# FY_-_SUPPLY_BOARD.net
KiCad netlist of a schematic drawn in EAGLE
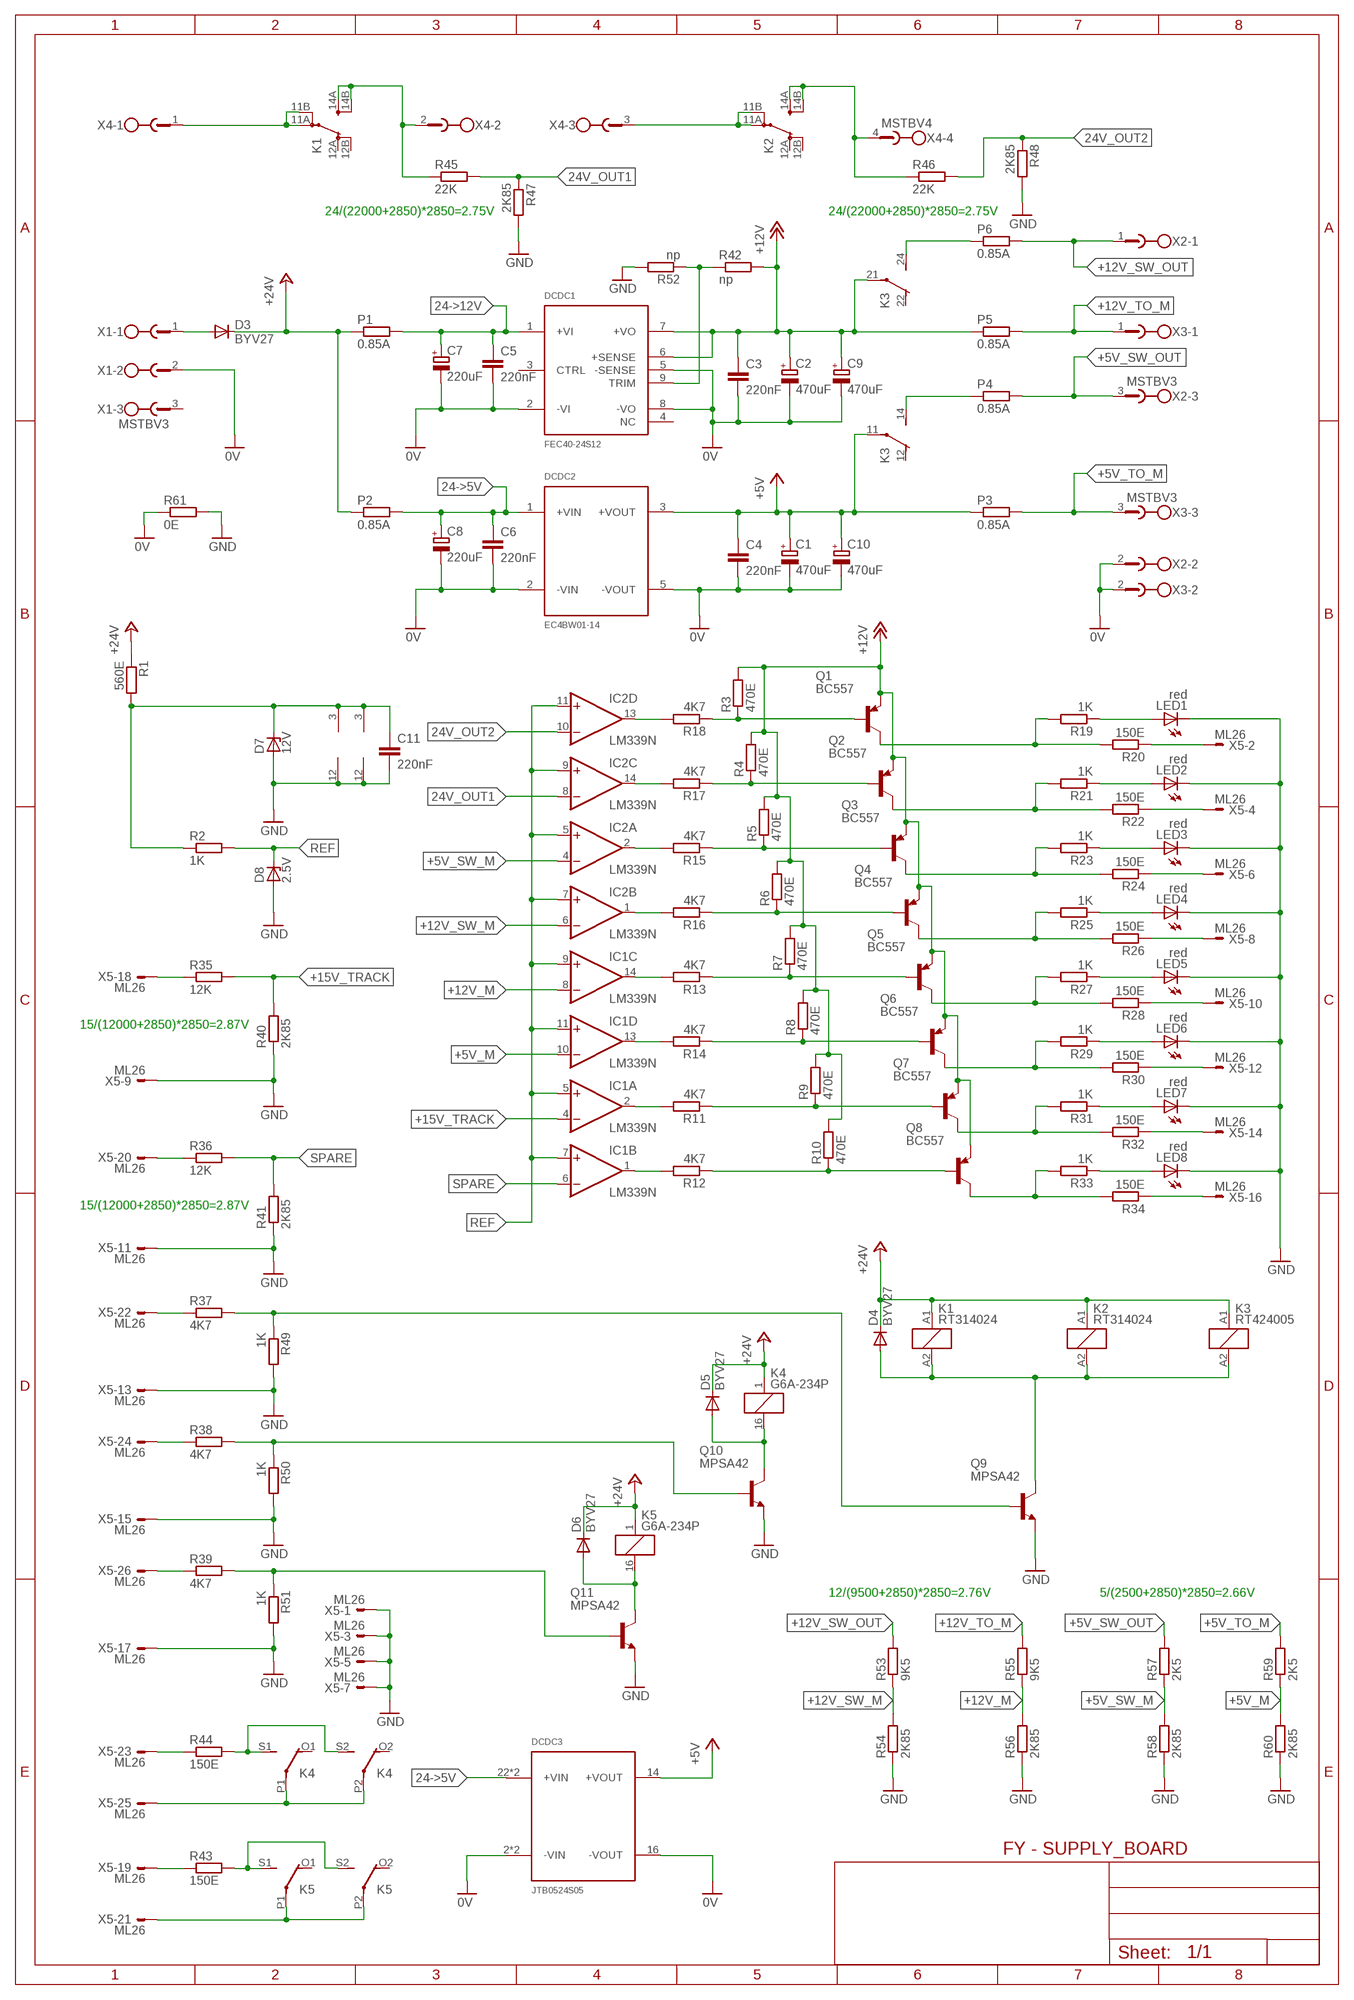
[diagram p0: schematic, sheet 1]

(export (version "E")
  (design (tool "Eeschema 10.0.6"))
  (components
    (comp (ref "C1")
      (value "470uF")
      (footprint "eagle-import:E5-10,5")
      (libsource (lib "eagle-import") (part "CPOL-EUE5-10.5"))
    )
    (comp (ref "C2")
      (value "470uF")
      (footprint "eagle-import:E5-10,5")
      (libsource (lib "eagle-import") (part "CPOL-EUE5-10.5"))
    )
    (comp (ref "C3")
      (value "220nF")
      (footprint "eagle-import:C050-025X075")
      (libsource (lib "eagle-import") (part "C-EU050-025X075"))
    )
    (comp (ref "C4")
      (value "220nF")
      (footprint "eagle-import:C050-025X075")
      (libsource (lib "eagle-import") (part "C-EU050-025X075"))
    )
    (comp (ref "C5")
      (value "220nF")
      (footprint "eagle-import:C050-025X075")
      (libsource (lib "eagle-import") (part "C-EU050-025X075"))
    )
    (comp (ref "C6")
      (value "220nF")
      (footprint "eagle-import:C050-025X075")
      (libsource (lib "eagle-import") (part "C-EU050-025X075"))
    )
    (comp (ref "C7")
      (value "220uF")
      (footprint "eagle-import:E5-10,5")
      (libsource (lib "eagle-import") (part "CPOL-EUE5-10.5"))
    )
    (comp (ref "C8")
      (value "220uF")
      (footprint "eagle-import:E5-10,5")
      (libsource (lib "eagle-import") (part "CPOL-EUE5-10.5"))
    )
    (comp (ref "C9")
      (value "470uF")
      (footprint "eagle-import:E5-10,5")
      (libsource (lib "eagle-import") (part "CPOL-EUE5-10.5"))
    )
    (comp (ref "C10")
      (value "470uF")
      (footprint "eagle-import:E5-10,5")
      (libsource (lib "eagle-import") (part "CPOL-EUE5-10.5"))
    )
    (comp (ref "C11")
      (value "220nF")
      (footprint "eagle-import:C050-025X075")
      (libsource (lib "eagle-import") (part "C-EU050-025X075"))
    )
    (comp (ref "D3")
      (value "BYV27")
      (footprint "eagle-import:SOD57-10")
      (libsource (lib "eagle-import") (part "BYV27"))
    )
    (comp (ref "D4")
      (value "BYV27")
      (footprint "eagle-import:SOD57-10")
      (libsource (lib "eagle-import") (part "BYV27"))
    )
    (comp (ref "D5")
      (value "BYV27")
      (footprint "eagle-import:SOD57-10")
      (libsource (lib "eagle-import") (part "BYV27"))
    )
    (comp (ref "D6")
      (value "BYV27")
      (footprint "eagle-import:SOD57-10")
      (libsource (lib "eagle-import") (part "BYV27"))
    )
    (comp (ref "D7")
      (value "12V")
      (footprint "eagle-import:ZDIO-7.5")
      (libsource (lib "eagle-import") (part "ZENER-DIODEZD-7.5"))
    )
    (comp (ref "D8")
      (value "2.5V")
      (footprint "eagle-import:ZDIO-7.5")
      (libsource (lib "eagle-import") (part "ZENER-DIODEZD-7.5"))
    )
    (comp (ref "DCDC1")
      (value "FEC40-24S12")
      (footprint "eagle-import:FEC40-24S12")
      (libsource (lib "eagle-import") (part "FEC40-24S12"))
    )
    (comp (ref "DCDC2")
      (value "EC4BW01-14")
      (footprint "eagle-import:EC4BW01-14")
      (libsource (lib "eagle-import") (part "EC4BW01-14"))
    )
    (comp (ref "DCDC3")
      (value "JTB0524S05")
      (footprint "eagle-import:XP_POWER_5W")
      (libsource (lib "eagle-import") (part "JTB0524S05_JTB0524S05"))
    )
    (comp (ref "IC1")
      (value "LM339N")
      (footprint "eagle-import:DIL14")
      (libsource (lib "eagle-import") (part "LM339N"))
    )
    (comp (ref "IC2")
      (value "LM339N")
      (footprint "eagle-import:DIL14")
      (libsource (lib "eagle-import") (part "LM339N"))
    )
    (comp (ref "K1")
      (value "RT314024")
      (footprint "eagle-import:RT-C_O16A5")
      (fields (field (name "MF") "TYCO ELECTRONICS"))
      (libsource (lib "eagle-import") (part "RT314024"))
    )
    (comp (ref "K2")
      (value "RT314024")
      (footprint "eagle-import:RT-C_O16A5")
      (fields (field (name "MF") "TYCO ELECTRONICS"))
      (libsource (lib "eagle-import") (part "RT314024"))
    )
    (comp (ref "K3")
      (value "RT424005")
      (footprint "eagle-import:RT2C_O")
      (libsource (lib "eagle-import") (part "RT42?4005"))
    )
    (comp (ref "K4")
      (value "G6A-234P")
      (footprint "eagle-import:G6A-234P")
      (libsource (lib "eagle-import") (part "G6A-234P"))
    )
    (comp (ref "K5")
      (value "G6A-234P")
      (footprint "eagle-import:G6A-234P")
      (libsource (lib "eagle-import") (part "G6A-234P"))
    )
    (comp (ref "LED1")
      (value "red")
      (footprint "eagle-import:LED3MM")
      (libsource (lib "eagle-import") (part "LED3MM"))
    )
    (comp (ref "LED2")
      (value "red")
      (footprint "eagle-import:LED3MM")
      (libsource (lib "eagle-import") (part "LED3MM"))
    )
    (comp (ref "LED3")
      (value "red")
      (footprint "eagle-import:LED3MM")
      (libsource (lib "eagle-import") (part "LED3MM"))
    )
    (comp (ref "LED4")
      (value "red")
      (footprint "eagle-import:LED3MM")
      (libsource (lib "eagle-import") (part "LED3MM"))
    )
    (comp (ref "LED5")
      (value "red")
      (footprint "eagle-import:LED3MM")
      (libsource (lib "eagle-import") (part "LED3MM"))
    )
    (comp (ref "LED6")
      (value "red")
      (footprint "eagle-import:LED3MM")
      (libsource (lib "eagle-import") (part "LED3MM"))
    )
    (comp (ref "LED7")
      (value "red")
      (footprint "eagle-import:LED3MM")
      (libsource (lib "eagle-import") (part "LED3MM"))
    )
    (comp (ref "LED8")
      (value "red")
      (footprint "eagle-import:LED3MM")
      (libsource (lib "eagle-import") (part "LED3MM"))
    )
    (comp (ref "P1")
      (value "0.85A")
      (footprint "eagle-import:0207_7")
      (libsource (lib "eagle-import") (part "R-EU_0207/7"))
    )
    (comp (ref "P2")
      (value "0.85A")
      (footprint "eagle-import:0207_7")
      (libsource (lib "eagle-import") (part "R-EU_0207/7"))
    )
    (comp (ref "P3")
      (value "0.85A")
      (footprint "eagle-import:0207_7")
      (libsource (lib "eagle-import") (part "R-EU_0207/7"))
    )
    (comp (ref "P4")
      (value "0.85A")
      (footprint "eagle-import:0207_7")
      (libsource (lib "eagle-import") (part "R-EU_0207/7"))
    )
    (comp (ref "P5")
      (value "0.85A")
      (footprint "eagle-import:0207_7")
      (libsource (lib "eagle-import") (part "R-EU_0207/7"))
    )
    (comp (ref "P6")
      (value "0.85A")
      (footprint "eagle-import:0207_7")
      (libsource (lib "eagle-import") (part "R-EU_0207/7"))
    )
    (comp (ref "Q1")
      (value "BC557")
      (footprint "eagle-import:TO92-EBC")
      (libsource (lib "eagle-import") (part "BC557"))
    )
    (comp (ref "Q2")
      (value "BC557")
      (footprint "eagle-import:TO92-EBC")
      (libsource (lib "eagle-import") (part "BC557"))
    )
    (comp (ref "Q3")
      (value "BC557")
      (footprint "eagle-import:TO92-EBC")
      (libsource (lib "eagle-import") (part "BC557"))
    )
    (comp (ref "Q4")
      (value "BC557")
      (footprint "eagle-import:TO92-EBC")
      (libsource (lib "eagle-import") (part "BC557"))
    )
    (comp (ref "Q5")
      (value "BC557")
      (footprint "eagle-import:TO92-EBC")
      (libsource (lib "eagle-import") (part "BC557"))
    )
    (comp (ref "Q6")
      (value "BC557")
      (footprint "eagle-import:TO92-EBC")
      (libsource (lib "eagle-import") (part "BC557"))
    )
    (comp (ref "Q7")
      (value "BC557")
      (footprint "eagle-import:TO92-EBC")
      (libsource (lib "eagle-import") (part "BC557"))
    )
    (comp (ref "Q8")
      (value "BC557")
      (footprint "eagle-import:TO92-EBC")
      (libsource (lib "eagle-import") (part "BC557"))
    )
    (comp (ref "Q9")
      (value "MPSA42")
      (footprint "eagle-import:TO92-CBE")
      (libsource (lib "eagle-import") (part "MPSA42TO92-CBE"))
    )
    (comp (ref "Q10")
      (value "MPSA42")
      (footprint "eagle-import:TO92-CBE")
      (libsource (lib "eagle-import") (part "MPSA42TO92-CBE"))
    )
    (comp (ref "Q11")
      (value "MPSA42")
      (footprint "eagle-import:TO92-CBE")
      (libsource (lib "eagle-import") (part "MPSA42TO92-CBE"))
    )
    (comp (ref "R1")
      (value "560E")
      (footprint "eagle-import:0411_15")
      (libsource (lib "eagle-import") (part "R-EU_0411/15"))
    )
    (comp (ref "R2")
      (value "1K")
      (footprint "eagle-import:0207_10")
      (libsource (lib "eagle-import") (part "R-EU_0207/10"))
    )
    (comp (ref "R3")
      (value "470E")
      (footprint "eagle-import:0207_10")
      (libsource (lib "eagle-import") (part "R-EU_0207/10"))
    )
    (comp (ref "R4")
      (value "470E")
      (footprint "eagle-import:0207_10")
      (libsource (lib "eagle-import") (part "R-EU_0207/10"))
    )
    (comp (ref "R5")
      (value "470E")
      (footprint "eagle-import:0207_10")
      (libsource (lib "eagle-import") (part "R-EU_0207/10"))
    )
    (comp (ref "R6")
      (value "470E")
      (footprint "eagle-import:0207_10")
      (libsource (lib "eagle-import") (part "R-EU_0207/10"))
    )
    (comp (ref "R7")
      (value "470E")
      (footprint "eagle-import:0207_10")
      (libsource (lib "eagle-import") (part "R-EU_0207/10"))
    )
    (comp (ref "R8")
      (value "470E")
      (footprint "eagle-import:0207_10")
      (libsource (lib "eagle-import") (part "R-EU_0207/10"))
    )
    (comp (ref "R9")
      (value "470E")
      (footprint "eagle-import:0207_10")
      (libsource (lib "eagle-import") (part "R-EU_0207/10"))
    )
    (comp (ref "R10")
      (value "470E")
      (footprint "eagle-import:0207_10")
      (libsource (lib "eagle-import") (part "R-EU_0207/10"))
    )
    (comp (ref "R11")
      (value "4K7")
      (footprint "eagle-import:0207_10")
      (libsource (lib "eagle-import") (part "R-EU_0207/10"))
    )
    (comp (ref "R12")
      (value "4K7")
      (footprint "eagle-import:0207_10")
      (libsource (lib "eagle-import") (part "R-EU_0207/10"))
    )
    (comp (ref "R13")
      (value "4K7")
      (footprint "eagle-import:0207_10")
      (libsource (lib "eagle-import") (part "R-EU_0207/10"))
    )
    (comp (ref "R14")
      (value "4K7")
      (footprint "eagle-import:0207_10")
      (libsource (lib "eagle-import") (part "R-EU_0207/10"))
    )
    (comp (ref "R15")
      (value "4K7")
      (footprint "eagle-import:0207_10")
      (libsource (lib "eagle-import") (part "R-EU_0207/10"))
    )
    (comp (ref "R16")
      (value "4K7")
      (footprint "eagle-import:0207_10")
      (libsource (lib "eagle-import") (part "R-EU_0207/10"))
    )
    (comp (ref "R17")
      (value "4K7")
      (footprint "eagle-import:0207_10")
      (libsource (lib "eagle-import") (part "R-EU_0207/10"))
    )
    (comp (ref "R18")
      (value "4K7")
      (footprint "eagle-import:0207_10")
      (libsource (lib "eagle-import") (part "R-EU_0207/10"))
    )
    (comp (ref "R19")
      (value "1K")
      (footprint "eagle-import:0207_10")
      (libsource (lib "eagle-import") (part "R-EU_0207/10"))
    )
    (comp (ref "R20")
      (value "150E")
      (footprint "eagle-import:0207_10")
      (libsource (lib "eagle-import") (part "R-EU_0207/10"))
    )
    (comp (ref "R21")
      (value "1K")
      (footprint "eagle-import:0207_10")
      (libsource (lib "eagle-import") (part "R-EU_0207/10"))
    )
    (comp (ref "R22")
      (value "150E")
      (footprint "eagle-import:0207_10")
      (libsource (lib "eagle-import") (part "R-EU_0207/10"))
    )
    (comp (ref "R23")
      (value "1K")
      (footprint "eagle-import:0207_10")
      (libsource (lib "eagle-import") (part "R-EU_0207/10"))
    )
    (comp (ref "R24")
      (value "150E")
      (footprint "eagle-import:0207_10")
      (libsource (lib "eagle-import") (part "R-EU_0207/10"))
    )
    (comp (ref "R25")
      (value "1K")
      (footprint "eagle-import:0207_10")
      (libsource (lib "eagle-import") (part "R-EU_0207/10"))
    )
    (comp (ref "R26")
      (value "150E")
      (footprint "eagle-import:0207_10")
      (libsource (lib "eagle-import") (part "R-EU_0207/10"))
    )
    (comp (ref "R27")
      (value "1K")
      (footprint "eagle-import:0207_10")
      (libsource (lib "eagle-import") (part "R-EU_0207/10"))
    )
    (comp (ref "R28")
      (value "150E")
      (footprint "eagle-import:0207_10")
      (libsource (lib "eagle-import") (part "R-EU_0207/10"))
    )
    (comp (ref "R29")
      (value "1K")
      (footprint "eagle-import:0207_10")
      (libsource (lib "eagle-import") (part "R-EU_0207/10"))
    )
    (comp (ref "R30")
      (value "150E")
      (footprint "eagle-import:0207_10")
      (libsource (lib "eagle-import") (part "R-EU_0207/10"))
    )
    (comp (ref "R31")
      (value "1K")
      (footprint "eagle-import:0207_10")
      (libsource (lib "eagle-import") (part "R-EU_0207/10"))
    )
    (comp (ref "R32")
      (value "150E")
      (footprint "eagle-import:0207_10")
      (libsource (lib "eagle-import") (part "R-EU_0207/10"))
    )
    (comp (ref "R33")
      (value "1K")
      (footprint "eagle-import:0207_10")
      (libsource (lib "eagle-import") (part "R-EU_0207/10"))
    )
    (comp (ref "R34")
      (value "150E")
      (footprint "eagle-import:0207_10")
      (libsource (lib "eagle-import") (part "R-EU_0207/10"))
    )
    (comp (ref "R35")
      (value "12K")
      (footprint "eagle-import:0207_10")
      (libsource (lib "eagle-import") (part "R-EU_0207/10"))
    )
    (comp (ref "R36")
      (value "12K")
      (footprint "eagle-import:0207_10")
      (libsource (lib "eagle-import") (part "R-EU_0207/10"))
    )
    (comp (ref "R37")
      (value "4K7")
      (footprint "eagle-import:0207_10")
      (libsource (lib "eagle-import") (part "R-EU_0207/10"))
    )
    (comp (ref "R38")
      (value "4K7")
      (footprint "eagle-import:0207_10")
      (libsource (lib "eagle-import") (part "R-EU_0207/10"))
    )
    (comp (ref "R39")
      (value "4K7")
      (footprint "eagle-import:0207_10")
      (libsource (lib "eagle-import") (part "R-EU_0207/10"))
    )
    (comp (ref "R40")
      (value "2K85")
      (footprint "eagle-import:0207_10")
      (libsource (lib "eagle-import") (part "R-EU_0207/10"))
    )
    (comp (ref "R41")
      (value "2K85")
      (footprint "eagle-import:0207_10")
      (libsource (lib "eagle-import") (part "R-EU_0207/10"))
    )
    (comp (ref "R42")
      (value "np")
      (footprint "eagle-import:0207_10")
      (libsource (lib "eagle-import") (part "R-EU_0207/10"))
    )
    (comp (ref "R43")
      (value "150E")
      (footprint "eagle-import:0922_11")
      (libsource (lib "eagle-import") (part "R-EU_0922/11"))
    )
    (comp (ref "R44")
      (value "150E")
      (footprint "eagle-import:0922_11")
      (libsource (lib "eagle-import") (part "R-EU_0922/11"))
    )
    (comp (ref "R45")
      (value "22K")
      (footprint "eagle-import:0207_10")
      (libsource (lib "eagle-import") (part "R-EU_0207/10"))
    )
    (comp (ref "R46")
      (value "22K")
      (footprint "eagle-import:0207_10")
      (libsource (lib "eagle-import") (part "R-EU_0207/10"))
    )
    (comp (ref "R47")
      (value "2K85")
      (footprint "eagle-import:0207_10")
      (libsource (lib "eagle-import") (part "R-EU_0207/10"))
    )
    (comp (ref "R48")
      (value "2K85")
      (footprint "eagle-import:0207_10")
      (libsource (lib "eagle-import") (part "R-EU_0207/10"))
    )
    (comp (ref "R49")
      (value "1K")
      (footprint "eagle-import:0207_10")
      (libsource (lib "eagle-import") (part "R-EU_0207/10"))
    )
    (comp (ref "R50")
      (value "1K")
      (footprint "eagle-import:0207_10")
      (libsource (lib "eagle-import") (part "R-EU_0207/10"))
    )
    (comp (ref "R51")
      (value "1K")
      (footprint "eagle-import:0207_10")
      (libsource (lib "eagle-import") (part "R-EU_0207/10"))
    )
    (comp (ref "R52")
      (value "np")
      (footprint "eagle-import:0207_10")
      (libsource (lib "eagle-import") (part "R-EU_0207/10"))
    )
    (comp (ref "R53")
      (value "9K5")
      (footprint "eagle-import:0207_10")
      (libsource (lib "eagle-import") (part "R-EU_0207/10"))
    )
    (comp (ref "R54")
      (value "2K85")
      (footprint "eagle-import:0207_10")
      (libsource (lib "eagle-import") (part "R-EU_0207/10"))
    )
    (comp (ref "R55")
      (value "9K5")
      (footprint "eagle-import:0207_10")
      (libsource (lib "eagle-import") (part "R-EU_0207/10"))
    )
    (comp (ref "R56")
      (value "2K85")
      (footprint "eagle-import:0207_10")
      (libsource (lib "eagle-import") (part "R-EU_0207/10"))
    )
    (comp (ref "R57")
      (value "2K5")
      (footprint "eagle-import:0207_10")
      (libsource (lib "eagle-import") (part "R-EU_0207/10"))
    )
    (comp (ref "R58")
      (value "2K85")
      (footprint "eagle-import:0207_10")
      (libsource (lib "eagle-import") (part "R-EU_0207/10"))
    )
    (comp (ref "R59")
      (value "2K5")
      (footprint "eagle-import:0207_10")
      (libsource (lib "eagle-import") (part "R-EU_0207/10"))
    )
    (comp (ref "R60")
      (value "2K85")
      (footprint "eagle-import:0207_10")
      (libsource (lib "eagle-import") (part "R-EU_0207/10"))
    )
    (comp (ref "R61")
      (value "0E")
      (footprint "eagle-import:0204V")
      (libsource (lib "eagle-import") (part "resistor_R-EU_0204/2V"))
    )
    (comp (ref "X1")
      (value "MSTBV3")
      (footprint "eagle-import:MSTBV3")
      (fields (field (name "MPN") "MSTBV 2,5/3-GF-5.08"))
      (libsource (lib "eagle-import") (part "MSTBV3"))
    )
    (comp (ref "X2")
      (value "MSTBV3")
      (footprint "eagle-import:MSTBV3")
      (fields (field (name "MPN") "MSTBV 2,5/3-GF-5.08"))
      (libsource (lib "eagle-import") (part "MSTBV3"))
    )
    (comp (ref "X3")
      (value "MSTBV3")
      (footprint "eagle-import:MSTBV3")
      (fields (field (name "MPN") "MSTBV 2,5/3-GF-5.08"))
      (libsource (lib "eagle-import") (part "MSTBV3"))
    )
    (comp (ref "X4")
      (value "MSTBV4")
      (footprint "eagle-import:MSTBV4")
      (fields (field (name "MPN") "MSTBV 2,5/4-GF-5.08"))
      (libsource (lib "eagle-import") (part "MSTBV4"))
    )
    (comp (ref "X5")
      (value "ML26")
      (footprint "eagle-import:ML26")
      (libsource (lib "eagle-import") (part "ML26?E"))
    )
  )
  (nets
    (net (code "1") (name "+5V") (class "Default")
      (node (ref "C1") (pin "+") (pinfunction "+_+") (pintype "passive"))
      (node (ref "C10") (pin "+") (pinfunction "+_+") (pintype "passive"))
      (node (ref "C4") (pin "1") (pinfunction "1_1") (pintype "passive"))
      (node (ref "DCDC2") (pin "3") (pinfunction "+VOUT_3") (pintype "passive"))
      (node (ref "DCDC3") (pin "14") (pinfunction "+VOUT_14") (pintype "passive"))
      (node (ref "K3") (pin "11") (pinfunction "P_11") (pintype "passive"))
      (node (ref "P3") (pin "1") (pinfunction "1_1") (pintype "passive"))
    )
    (net (code "2") (name "+5V_M") (class "Default")
      (node (ref "IC1") (pin "10") (pinfunction "-IN_10") (pintype "input"))
      (node (ref "R59") (pin "1") (pinfunction "1_1") (pintype "passive"))
      (node (ref "R60") (pin "2") (pinfunction "2_2") (pintype "passive"))
    )
    (net (code "3") (name "+5V_SW_M") (class "Default")
      (node (ref "IC2") (pin "4") (pinfunction "-IN_4") (pintype "input"))
      (node (ref "R57") (pin "1") (pinfunction "1_1") (pintype "passive"))
      (node (ref "R58") (pin "2") (pinfunction "2_2") (pintype "passive"))
    )
    (net (code "4") (name "+5V_SW_OUT") (class "Default")
      (node (ref "P4") (pin "2") (pinfunction "2_2") (pintype "passive"))
      (node (ref "R57") (pin "2") (pinfunction "2_2") (pintype "passive"))
      (node (ref "X2") (pin "3") (pinfunction "1_3") (pintype "passive"))
    )
    (net (code "5") (name "+5V_TO_M") (class "Default")
      (node (ref "P3") (pin "2") (pinfunction "2_2") (pintype "passive"))
      (node (ref "R59") (pin "2") (pinfunction "2_2") (pintype "passive"))
      (node (ref "X3") (pin "3") (pinfunction "1_3") (pintype "passive"))
    )
    (net (code "6") (name "+12V") (class "Default")
      (node (ref "C2") (pin "+") (pinfunction "+_+") (pintype "passive"))
      (node (ref "C3") (pin "1") (pinfunction "1_1") (pintype "passive"))
      (node (ref "C9") (pin "+") (pinfunction "+_+") (pintype "passive"))
      (node (ref "DCDC1") (pin "6") (pinfunction "+SENSE_6") (pintype "passive"))
      (node (ref "DCDC1") (pin "7") (pinfunction "+VO_7") (pintype "passive"))
      (node (ref "K3") (pin "21") (pinfunction "P_21") (pintype "passive"))
      (node (ref "P5") (pin "1") (pinfunction "1_1") (pintype "passive"))
      (node (ref "Q1") (pin "E") (pinfunction "E_E") (pintype "passive"))
      (node (ref "Q2") (pin "E") (pinfunction "E_E") (pintype "passive"))
      (node (ref "Q3") (pin "E") (pinfunction "E_E") (pintype "passive"))
      (node (ref "Q4") (pin "E") (pinfunction "E_E") (pintype "passive"))
      (node (ref "Q5") (pin "E") (pinfunction "E_E") (pintype "passive"))
      (node (ref "Q6") (pin "E") (pinfunction "E_E") (pintype "passive"))
      (node (ref "Q7") (pin "E") (pinfunction "E_E") (pintype "passive"))
      (node (ref "Q8") (pin "E") (pinfunction "E_E") (pintype "passive"))
      (node (ref "R10") (pin "2") (pinfunction "2_2") (pintype "passive"))
      (node (ref "R3") (pin "2") (pinfunction "2_2") (pintype "passive"))
      (node (ref "R4") (pin "2") (pinfunction "2_2") (pintype "passive"))
      (node (ref "R42") (pin "2") (pinfunction "2_2") (pintype "passive"))
      (node (ref "R5") (pin "2") (pinfunction "2_2") (pintype "passive"))
      (node (ref "R6") (pin "2") (pinfunction "2_2") (pintype "passive"))
      (node (ref "R7") (pin "2") (pinfunction "2_2") (pintype "passive"))
      (node (ref "R8") (pin "2") (pinfunction "2_2") (pintype "passive"))
      (node (ref "R9") (pin "2") (pinfunction "2_2") (pintype "passive"))
    )
    (net (code "7") (name "+12V_M") (class "Default")
      (node (ref "IC1") (pin "8") (pinfunction "-IN_8") (pintype "input"))
      (node (ref "R55") (pin "1") (pinfunction "1_1") (pintype "passive"))
      (node (ref "R56") (pin "2") (pinfunction "2_2") (pintype "passive"))
    )
    (net (code "8") (name "+12V_SW_M") (class "Default")
      (node (ref "IC2") (pin "6") (pinfunction "-IN_6") (pintype "input"))
      (node (ref "R53") (pin "1") (pinfunction "1_1") (pintype "passive"))
      (node (ref "R54") (pin "2") (pinfunction "2_2") (pintype "passive"))
    )
    (net (code "9") (name "+12V_SW_OUT") (class "Default")
      (node (ref "P6") (pin "2") (pinfunction "2_2") (pintype "passive"))
      (node (ref "R53") (pin "2") (pinfunction "2_2") (pintype "passive"))
      (node (ref "X2") (pin "1") (pinfunction "1_1") (pintype "passive"))
    )
    (net (code "10") (name "+12V_TO_M") (class "Default")
      (node (ref "P5") (pin "2") (pinfunction "2_2") (pintype "passive"))
      (node (ref "R55") (pin "2") (pinfunction "2_2") (pintype "passive"))
      (node (ref "X3") (pin "1") (pinfunction "1_1") (pintype "passive"))
    )
    (net (code "11") (name "+15V_TRACK") (class "Default")
      (node (ref "IC1") (pin "4") (pinfunction "-IN_4") (pintype "input"))
      (node (ref "R35") (pin "2") (pinfunction "2_2") (pintype "passive"))
      (node (ref "R40") (pin "2") (pinfunction "2_2") (pintype "passive"))
    )
    (net (code "12") (name "+24V") (class "Default")
      (node (ref "D3") (pin "C") (pinfunction "C_C") (pintype "passive"))
      (node (ref "D4") (pin "C") (pinfunction "C_C") (pintype "passive"))
      (node (ref "D5") (pin "C") (pinfunction "C_C") (pintype "passive"))
      (node (ref "D6") (pin "C") (pinfunction "C_C") (pintype "passive"))
      (node (ref "K1") (pin "A1") (pinfunction "1_A1") (pintype "passive"))
      (node (ref "K2") (pin "A1") (pinfunction "1_A1") (pintype "passive"))
      (node (ref "K3") (pin "A1") (pinfunction "1_A1") (pintype "passive"))
      (node (ref "K4") (pin "1") (pinfunction "1_1") (pintype "passive"))
      (node (ref "K5") (pin "1") (pinfunction "1_1") (pintype "passive"))
      (node (ref "P1") (pin "1") (pinfunction "1_1") (pintype "passive"))
      (node (ref "P2") (pin "1") (pinfunction "1_1") (pintype "passive"))
      (node (ref "R1") (pin "1") (pinfunction "1_1") (pintype "passive"))
    )
    (net (code "13") (name "0V") (class "Default")
      (node (ref "C1") (pin "-") (pinfunction "-_-") (pintype "passive"))
      (node (ref "C10") (pin "-") (pinfunction "-_-") (pintype "passive"))
      (node (ref "C2") (pin "-") (pinfunction "-_-") (pintype "passive"))
      (node (ref "C3") (pin "2") (pinfunction "2_2") (pintype "passive"))
      (node (ref "C4") (pin "2") (pinfunction "2_2") (pintype "passive"))
      (node (ref "C5") (pin "2") (pinfunction "2_2") (pintype "passive"))
      (node (ref "C6") (pin "2") (pinfunction "2_2") (pintype "passive"))
      (node (ref "C7") (pin "-") (pinfunction "-_-") (pintype "passive"))
      (node (ref "C8") (pin "-") (pinfunction "-_-") (pintype "passive"))
      (node (ref "C9") (pin "-") (pinfunction "-_-") (pintype "passive"))
      (node (ref "DCDC1") (pin "2") (pinfunction "-VI_2") (pintype "passive"))
      (node (ref "DCDC1") (pin "5") (pinfunction "-SENSE_5") (pintype "passive"))
      (node (ref "DCDC1") (pin "8") (pinfunction "-VO_8") (pintype "passive"))
      (node (ref "DCDC2") (pin "2") (pinfunction "-VIN_2") (pintype "passive"))
      (node (ref "DCDC2") (pin "5") (pinfunction "-VOUT_5") (pintype "passive"))
      (node (ref "DCDC3") (pin "16") (pinfunction "-VOUT_16") (pintype "passive"))
      (node (ref "DCDC3") (pin "2") (pinfunction "-VIN_2") (pintype "passive"))
      (node (ref "DCDC3") (pin "3") (pinfunction "-VIN_3") (pintype "passive"))
      (node (ref "R61") (pin "1") (pinfunction "1_1") (pintype "passive"))
      (node (ref "X1") (pin "2") (pinfunction "1_2") (pintype "passive"))
      (node (ref "X2") (pin "2") (pinfunction "1_2") (pintype "passive"))
      (node (ref "X3") (pin "2") (pinfunction "1_2") (pintype "passive"))
    )
    (net (code "14") (name "24->5V") (class "Default")
      (node (ref "C6") (pin "1") (pinfunction "1_1") (pintype "passive"))
      (node (ref "C8") (pin "+") (pinfunction "+_+") (pintype "passive"))
      (node (ref "DCDC2") (pin "1") (pinfunction "+VIN_1") (pintype "passive"))
      (node (ref "DCDC3") (pin "22") (pinfunction "+VIN_22") (pintype "passive"))
      (node (ref "DCDC3") (pin "23") (pinfunction "+VIN_23") (pintype "passive"))
      (node (ref "P2") (pin "2") (pinfunction "2_2") (pintype "passive"))
    )
    (net (code "15") (name "24->12V") (class "Default")
      (node (ref "C5") (pin "1") (pinfunction "1_1") (pintype "passive"))
      (node (ref "C7") (pin "+") (pinfunction "+_+") (pintype "passive"))
      (node (ref "DCDC1") (pin "1") (pinfunction "+VI_1") (pintype "passive"))
      (node (ref "P1") (pin "2") (pinfunction "2_2") (pintype "passive"))
    )
    (net (code "16") (name "24V_OUT1") (class "Default")
      (node (ref "IC2") (pin "8") (pinfunction "-IN_8") (pintype "input"))
      (node (ref "R45") (pin "2") (pinfunction "2_2") (pintype "passive"))
      (node (ref "R47") (pin "1") (pinfunction "1_1") (pintype "passive"))
    )
    (net (code "17") (name "24V_OUT2") (class "Default")
      (node (ref "IC2") (pin "10") (pinfunction "-IN_10") (pintype "input"))
      (node (ref "R46") (pin "2") (pinfunction "2_2") (pintype "passive"))
      (node (ref "R48") (pin "1") (pinfunction "1_1") (pintype "passive"))
    )
    (net (code "18") (name "GND") (class "Default")
      (node (ref "C11") (pin "2") (pinfunction "2_2") (pintype "passive"))
      (node (ref "D7") (pin "A") (pinfunction "A_A") (pintype "passive"))
      (node (ref "D8") (pin "A") (pinfunction "A_A") (pintype "passive"))
      (node (ref "IC1") (pin "12") (pinfunction "GND_12") (pintype "power_in"))
      (node (ref "IC2") (pin "12") (pinfunction "GND_12") (pintype "power_in"))
      (node (ref "LED1") (pin "K") (pinfunction "C_K") (pintype "passive"))
      (node (ref "LED2") (pin "K") (pinfunction "C_K") (pintype "passive"))
      (node (ref "LED3") (pin "K") (pinfunction "C_K") (pintype "passive"))
      (node (ref "LED4") (pin "K") (pinfunction "C_K") (pintype "passive"))
      (node (ref "LED5") (pin "K") (pinfunction "C_K") (pintype "passive"))
      (node (ref "LED6") (pin "K") (pinfunction "C_K") (pintype "passive"))
      (node (ref "LED7") (pin "K") (pinfunction "C_K") (pintype "passive"))
      (node (ref "LED8") (pin "K") (pinfunction "C_K") (pintype "passive"))
      (node (ref "Q10") (pin "E") (pinfunction "E_E") (pintype "passive"))
      (node (ref "Q11") (pin "E") (pinfunction "E_E") (pintype "passive"))
      (node (ref "Q9") (pin "E") (pinfunction "E_E") (pintype "passive"))
      (node (ref "R40") (pin "1") (pinfunction "1_1") (pintype "passive"))
      (node (ref "R41") (pin "1") (pinfunction "1_1") (pintype "passive"))
      (node (ref "R47") (pin "2") (pinfunction "2_2") (pintype "passive"))
      (node (ref "R48") (pin "2") (pinfunction "2_2") (pintype "passive"))
      (node (ref "R49") (pin "2") (pinfunction "2_2") (pintype "passive"))
      (node (ref "R50") (pin "2") (pinfunction "2_2") (pintype "passive"))
      (node (ref "R51") (pin "2") (pinfunction "2_2") (pintype "passive"))
      (node (ref "R52") (pin "2") (pinfunction "2_2") (pintype "passive"))
      (node (ref "R54") (pin "1") (pinfunction "1_1") (pintype "passive"))
      (node (ref "R56") (pin "1") (pinfunction "1_1") (pintype "passive"))
      (node (ref "R58") (pin "1") (pinfunction "1_1") (pintype "passive"))
      (node (ref "R60") (pin "1") (pinfunction "1_1") (pintype "passive"))
      (node (ref "R61") (pin "2") (pinfunction "2_2") (pintype "passive"))
      (node (ref "X5") (pin "1") (pinfunction "S_1") (pintype "passive"))
      (node (ref "X5") (pin "11") (pinfunction "S_11") (pintype "passive"))
      (node (ref "X5") (pin "13") (pinfunction "S_13") (pintype "passive"))
      (node (ref "X5") (pin "15") (pinfunction "S_15") (pintype "passive"))
      (node (ref "X5") (pin "17") (pinfunction "S_17") (pintype "passive"))
      (node (ref "X5") (pin "3") (pinfunction "S_3") (pintype "passive"))
      (node (ref "X5") (pin "5") (pinfunction "S_5") (pintype "passive"))
      (node (ref "X5") (pin "7") (pinfunction "S_7") (pintype "passive"))
      (node (ref "X5") (pin "9") (pinfunction "S_9") (pintype "passive"))
    )
    (net (code "19") (name "Net-(D3-PadA)") (class "Default")
      (node (ref "D3") (pin "A") (pinfunction "A_A") (pintype "passive"))
      (node (ref "X1") (pin "1") (pinfunction "1_1") (pintype "passive"))
    )
    (net (code "20") (name "Net-(DCDC1-TRIM)") (class "Default")
      (node (ref "DCDC1") (pin "9") (pinfunction "TRIM_9") (pintype "passive"))
      (node (ref "R42") (pin "1") (pinfunction "1_1") (pintype "passive"))
      (node (ref "R52") (pin "1") (pinfunction "1_1") (pintype "passive"))
    )
    (net (code "21") (name "Net-(IC1A-OUT)") (class "Default")
      (node (ref "IC1") (pin "2") (pinfunction "OUT_2") (pintype "open_collector"))
      (node (ref "R11") (pin "2") (pinfunction "2_2") (pintype "passive"))
    )
    (net (code "22") (name "Net-(IC1B-OUT)") (class "Default")
      (node (ref "IC1") (pin "1") (pinfunction "OUT_1") (pintype "open_collector"))
      (node (ref "R12") (pin "2") (pinfunction "2_2") (pintype "passive"))
    )
    (net (code "23") (name "Net-(IC1C-OUT)") (class "Default")
      (node (ref "IC1") (pin "14") (pinfunction "OUT_14") (pintype "open_collector"))
      (node (ref "R13") (pin "2") (pinfunction "2_2") (pintype "passive"))
    )
    (net (code "24") (name "Net-(IC1D-OUT)") (class "Default")
      (node (ref "IC1") (pin "13") (pinfunction "OUT_13") (pintype "open_collector"))
      (node (ref "R14") (pin "2") (pinfunction "2_2") (pintype "passive"))
    )
    (net (code "25") (name "Net-(IC1E-V+)") (class "Default")
      (node (ref "C11") (pin "1") (pinfunction "1_1") (pintype "passive"))
      (node (ref "D7") (pin "C") (pinfunction "C_C") (pintype "passive"))
      (node (ref "IC1") (pin "3") (pinfunction "V+_3") (pintype "power_in"))
      (node (ref "IC2") (pin "3") (pinfunction "V+_3") (pintype "power_in"))
      (node (ref "R1") (pin "2") (pinfunction "2_2") (pintype "passive"))
      (node (ref "R2") (pin "1") (pinfunction "1_1") (pintype "passive"))
    )
    (net (code "26") (name "Net-(IC2A-OUT)") (class "Default")
      (node (ref "IC2") (pin "2") (pinfunction "OUT_2") (pintype "open_collector"))
      (node (ref "R15") (pin "2") (pinfunction "2_2") (pintype "passive"))
    )
    (net (code "27") (name "Net-(IC2B-OUT)") (class "Default")
      (node (ref "IC2") (pin "1") (pinfunction "OUT_1") (pintype "open_collector"))
      (node (ref "R16") (pin "2") (pinfunction "2_2") (pintype "passive"))
    )
    (net (code "28") (name "Net-(IC2C-OUT)") (class "Default")
      (node (ref "IC2") (pin "14") (pinfunction "OUT_14") (pintype "open_collector"))
      (node (ref "R17") (pin "2") (pinfunction "2_2") (pintype "passive"))
    )
    (net (code "29") (name "Net-(IC2D-OUT)") (class "Default")
      (node (ref "IC2") (pin "13") (pinfunction "OUT_13") (pintype "open_collector"))
      (node (ref "R18") (pin "2") (pinfunction "2_2") (pintype "passive"))
    )
    (net (code "30") (name "Net-(K1A-2)") (class "Default")
      (node (ref "D4") (pin "A") (pinfunction "A_A") (pintype "passive"))
      (node (ref "K1") (pin "A2") (pinfunction "2_A2") (pintype "passive"))
      (node (ref "K2") (pin "A2") (pinfunction "2_A2") (pintype "passive"))
      (node (ref "K3") (pin "A2") (pinfunction "2_A2") (pintype "passive"))
      (node (ref "Q9") (pin "C") (pinfunction "C_C") (pintype "passive"))
    )
    (net (code "31") (name "Net-(K1B-PA)") (class "Default")
      (node (ref "K1") (pin "11A") (pinfunction "PA_11A") (pintype "passive"))
      (node (ref "K1") (pin "11B") (pinfunction "PB_11B") (pintype "passive"))
      (node (ref "X4") (pin "1") (pinfunction "1_1") (pintype "passive"))
    )
    (net (code "32") (name "Net-(K1B-SA)") (class "Default")
      (node (ref "K1") (pin "14A") (pinfunction "SA_14A") (pintype "passive"))
      (node (ref "K1") (pin "14B") (pinfunction "SB_14B") (pintype "passive"))
      (node (ref "R45") (pin "1") (pinfunction "1_1") (pintype "passive"))
      (node (ref "X4") (pin "2") (pinfunction "1_2") (pintype "passive"))
    )
    (net (code "33") (name "Net-(K2B-PA)") (class "Default")
      (node (ref "K2") (pin "11A") (pinfunction "PA_11A") (pintype "passive"))
      (node (ref "K2") (pin "11B") (pinfunction "PB_11B") (pintype "passive"))
      (node (ref "X4") (pin "3") (pinfunction "1_3") (pintype "passive"))
    )
    (net (code "34") (name "Net-(K2B-SA)") (class "Default")
      (node (ref "K2") (pin "14A") (pinfunction "SA_14A") (pintype "passive"))
      (node (ref "K2") (pin "14B") (pinfunction "SB_14B") (pintype "passive"))
      (node (ref "R46") (pin "1") (pinfunction "1_1") (pintype "passive"))
      (node (ref "X4") (pin "4") (pinfunction "1_4") (pintype "passive"))
    )
    (net (code "35") (name "Net-(K3B-S)") (class "Default")
      (node (ref "K3") (pin "14") (pinfunction "S_14") (pintype "passive"))
      (node (ref "P4") (pin "1") (pinfunction "1_1") (pintype "passive"))
    )
    (net (code "36") (name "Net-(K3C-S)") (class "Default")
      (node (ref "K3") (pin "24") (pinfunction "S_24") (pintype "passive"))
      (node (ref "P6") (pin "1") (pinfunction "1_1") (pintype "passive"))
    )
    (net (code "37") (name "Net-(K4A-2)") (class "Default")
      (node (ref "D5") (pin "A") (pinfunction "A_A") (pintype "passive"))
      (node (ref "K4") (pin "16") (pinfunction "2_16") (pintype "passive"))
      (node (ref "Q10") (pin "C") (pinfunction "C_C") (pintype "passive"))
    )
    (net (code "38") (name "Net-(K4B-P)") (class "Default")
      (node (ref "K4") (pin "P1") (pinfunction "P_P1") (pintype "passive"))
      (node (ref "K4") (pin "P2") (pinfunction "P_P2") (pintype "passive"))
      (node (ref "X5") (pin "25") (pinfunction "S_25") (pintype "passive"))
    )
    (net (code "39") (name "Net-(K4B-S)") (class "Default")
      (node (ref "K4") (pin "S1") (pinfunction "S_S1") (pintype "passive"))
      (node (ref "K4") (pin "S2") (pinfunction "S_S2") (pintype "passive"))
      (node (ref "R44") (pin "2") (pinfunction "2_2") (pintype "passive"))
    )
    (net (code "40") (name "Net-(K5A-2)") (class "Default")
      (node (ref "D6") (pin "A") (pinfunction "A_A") (pintype "passive"))
      (node (ref "K5") (pin "16") (pinfunction "2_16") (pintype "passive"))
      (node (ref "Q11") (pin "C") (pinfunction "C_C") (pintype "passive"))
    )
    (net (code "41") (name "Net-(K5B-P)") (class "Default")
      (node (ref "K5") (pin "P1") (pinfunction "P_P1") (pintype "passive"))
      (node (ref "K5") (pin "P2") (pinfunction "P_P2") (pintype "passive"))
      (node (ref "X5") (pin "21") (pinfunction "S_21") (pintype "passive"))
    )
    (net (code "42") (name "Net-(K5B-S)") (class "Default")
      (node (ref "K5") (pin "S1") (pinfunction "S_S1") (pintype "passive"))
      (node (ref "K5") (pin "S2") (pinfunction "S_S2") (pintype "passive"))
      (node (ref "R43") (pin "2") (pinfunction "2_2") (pintype "passive"))
    )
    (net (code "43") (name "Net-(LED1-PadA)") (class "Default")
      (node (ref "LED1") (pin "A") (pinfunction "A_A") (pintype "passive"))
      (node (ref "R19") (pin "1") (pinfunction "1_1") (pintype "passive"))
    )
    (net (code "44") (name "Net-(LED2-PadA)") (class "Default")
      (node (ref "LED2") (pin "A") (pinfunction "A_A") (pintype "passive"))
      (node (ref "R21") (pin "1") (pinfunction "1_1") (pintype "passive"))
    )
    (net (code "45") (name "Net-(LED3-PadA)") (class "Default")
      (node (ref "LED3") (pin "A") (pinfunction "A_A") (pintype "passive"))
      (node (ref "R23") (pin "1") (pinfunction "1_1") (pintype "passive"))
    )
    (net (code "46") (name "Net-(LED4-PadA)") (class "Default")
      (node (ref "LED4") (pin "A") (pinfunction "A_A") (pintype "passive"))
      (node (ref "R25") (pin "1") (pinfunction "1_1") (pintype "passive"))
    )
    (net (code "47") (name "Net-(LED5-PadA)") (class "Default")
      (node (ref "LED5") (pin "A") (pinfunction "A_A") (pintype "passive"))
      (node (ref "R27") (pin "1") (pinfunction "1_1") (pintype "passive"))
    )
    (net (code "48") (name "Net-(LED6-PadA)") (class "Default")
      (node (ref "LED6") (pin "A") (pinfunction "A_A") (pintype "passive"))
      (node (ref "R29") (pin "1") (pinfunction "1_1") (pintype "passive"))
    )
    (net (code "49") (name "Net-(LED7-PadA)") (class "Default")
      (node (ref "LED7") (pin "A") (pinfunction "A_A") (pintype "passive"))
      (node (ref "R31") (pin "1") (pinfunction "1_1") (pintype "passive"))
    )
    (net (code "50") (name "Net-(LED8-PadA)") (class "Default")
      (node (ref "LED8") (pin "A") (pinfunction "A_A") (pintype "passive"))
      (node (ref "R33") (pin "1") (pinfunction "1_1") (pintype "passive"))
    )
    (net (code "51") (name "Net-(Q1-PadB)") (class "Default")
      (node (ref "Q1") (pin "B") (pinfunction "B_B") (pintype "passive"))
      (node (ref "R18") (pin "1") (pinfunction "1_1") (pintype "passive"))
      (node (ref "R3") (pin "1") (pinfunction "1_1") (pintype "passive"))
    )
    (net (code "52") (name "Net-(Q1-PadC)") (class "Default")
      (node (ref "Q1") (pin "C") (pinfunction "C_C") (pintype "passive"))
      (node (ref "R19") (pin "2") (pinfunction "2_2") (pintype "passive"))
      (node (ref "R20") (pin "2") (pinfunction "2_2") (pintype "passive"))
    )
    (net (code "53") (name "Net-(Q2-PadB)") (class "Default")
      (node (ref "Q2") (pin "B") (pinfunction "B_B") (pintype "passive"))
      (node (ref "R17") (pin "1") (pinfunction "1_1") (pintype "passive"))
      (node (ref "R4") (pin "1") (pinfunction "1_1") (pintype "passive"))
    )
    (net (code "54") (name "Net-(Q2-PadC)") (class "Default")
      (node (ref "Q2") (pin "C") (pinfunction "C_C") (pintype "passive"))
      (node (ref "R21") (pin "2") (pinfunction "2_2") (pintype "passive"))
      (node (ref "R22") (pin "2") (pinfunction "2_2") (pintype "passive"))
    )
    (net (code "55") (name "Net-(Q3-PadB)") (class "Default")
      (node (ref "Q3") (pin "B") (pinfunction "B_B") (pintype "passive"))
      (node (ref "R15") (pin "1") (pinfunction "1_1") (pintype "passive"))
      (node (ref "R5") (pin "1") (pinfunction "1_1") (pintype "passive"))
    )
    (net (code "56") (name "Net-(Q3-PadC)") (class "Default")
      (node (ref "Q3") (pin "C") (pinfunction "C_C") (pintype "passive"))
      (node (ref "R23") (pin "2") (pinfunction "2_2") (pintype "passive"))
      (node (ref "R24") (pin "2") (pinfunction "2_2") (pintype "passive"))
    )
    (net (code "57") (name "Net-(Q4-PadB)") (class "Default")
      (node (ref "Q4") (pin "B") (pinfunction "B_B") (pintype "passive"))
      (node (ref "R16") (pin "1") (pinfunction "1_1") (pintype "passive"))
      (node (ref "R6") (pin "1") (pinfunction "1_1") (pintype "passive"))
    )
    (net (code "58") (name "Net-(Q4-PadC)") (class "Default")
      (node (ref "Q4") (pin "C") (pinfunction "C_C") (pintype "passive"))
      (node (ref "R25") (pin "2") (pinfunction "2_2") (pintype "passive"))
      (node (ref "R26") (pin "2") (pinfunction "2_2") (pintype "passive"))
    )
    (net (code "59") (name "Net-(Q5-PadB)") (class "Default")
      (node (ref "Q5") (pin "B") (pinfunction "B_B") (pintype "passive"))
      (node (ref "R13") (pin "1") (pinfunction "1_1") (pintype "passive"))
      (node (ref "R7") (pin "1") (pinfunction "1_1") (pintype "passive"))
    )
    (net (code "60") (name "Net-(Q5-PadC)") (class "Default")
      (node (ref "Q5") (pin "C") (pinfunction "C_C") (pintype "passive"))
      (node (ref "R27") (pin "2") (pinfunction "2_2") (pintype "passive"))
      (node (ref "R28") (pin "2") (pinfunction "2_2") (pintype "passive"))
    )
    (net (code "61") (name "Net-(Q6-PadB)") (class "Default")
      (node (ref "Q6") (pin "B") (pinfunction "B_B") (pintype "passive"))
      (node (ref "R14") (pin "1") (pinfunction "1_1") (pintype "passive"))
      (node (ref "R8") (pin "1") (pinfunction "1_1") (pintype "passive"))
    )
    (net (code "62") (name "Net-(Q6-PadC)") (class "Default")
      (node (ref "Q6") (pin "C") (pinfunction "C_C") (pintype "passive"))
      (node (ref "R29") (pin "2") (pinfunction "2_2") (pintype "passive"))
      (node (ref "R30") (pin "2") (pinfunction "2_2") (pintype "passive"))
    )
    (net (code "63") (name "Net-(Q7-PadB)") (class "Default")
      (node (ref "Q7") (pin "B") (pinfunction "B_B") (pintype "passive"))
      (node (ref "R11") (pin "1") (pinfunction "1_1") (pintype "passive"))
      (node (ref "R9") (pin "1") (pinfunction "1_1") (pintype "passive"))
    )
    (net (code "64") (name "Net-(Q7-PadC)") (class "Default")
      (node (ref "Q7") (pin "C") (pinfunction "C_C") (pintype "passive"))
      (node (ref "R31") (pin "2") (pinfunction "2_2") (pintype "passive"))
      (node (ref "R32") (pin "2") (pinfunction "2_2") (pintype "passive"))
    )
    (net (code "65") (name "Net-(Q8-PadB)") (class "Default")
      (node (ref "Q8") (pin "B") (pinfunction "B_B") (pintype "passive"))
      (node (ref "R10") (pin "1") (pinfunction "1_1") (pintype "passive"))
      (node (ref "R12") (pin "1") (pinfunction "1_1") (pintype "passive"))
    )
    (net (code "66") (name "Net-(Q8-PadC)") (class "Default")
      (node (ref "Q8") (pin "C") (pinfunction "C_C") (pintype "passive"))
      (node (ref "R33") (pin "2") (pinfunction "2_2") (pintype "passive"))
      (node (ref "R34") (pin "2") (pinfunction "2_2") (pintype "passive"))
    )
    (net (code "67") (name "Net-(Q9-PadB)") (class "Default")
      (node (ref "Q9") (pin "B") (pinfunction "B_B") (pintype "passive"))
      (node (ref "R37") (pin "2") (pinfunction "2_2") (pintype "passive"))
      (node (ref "R49") (pin "1") (pinfunction "1_1") (pintype "passive"))
    )
    (net (code "68") (name "Net-(Q10-PadB)") (class "Default")
      (node (ref "Q10") (pin "B") (pinfunction "B_B") (pintype "passive"))
      (node (ref "R38") (pin "2") (pinfunction "2_2") (pintype "passive"))
      (node (ref "R50") (pin "1") (pinfunction "1_1") (pintype "passive"))
    )
    (net (code "69") (name "Net-(Q11-PadB)") (class "Default")
      (node (ref "Q11") (pin "B") (pinfunction "B_B") (pintype "passive"))
      (node (ref "R39") (pin "2") (pinfunction "2_2") (pintype "passive"))
      (node (ref "R51") (pin "1") (pinfunction "1_1") (pintype "passive"))
    )
    (net (code "70") (name "Net-(X5B-S)") (class "Default")
      (node (ref "R28") (pin "1") (pinfunction "1_1") (pintype "passive"))
      (node (ref "X5") (pin "10") (pinfunction "S_10") (pintype "passive"))
    )
    (net (code "71") (name "Net-(X5D-S)") (class "Default")
      (node (ref "R30") (pin "1") (pinfunction "1_1") (pintype "passive"))
      (node (ref "X5") (pin "12") (pinfunction "S_12") (pintype "passive"))
    )
    (net (code "72") (name "Net-(X5F-S)") (class "Default")
      (node (ref "R32") (pin "1") (pinfunction "1_1") (pintype "passive"))
      (node (ref "X5") (pin "14") (pinfunction "S_14") (pintype "passive"))
    )
    (net (code "73") (name "Net-(X5H-S)") (class "Default")
      (node (ref "R34") (pin "1") (pinfunction "1_1") (pintype "passive"))
      (node (ref "X5") (pin "16") (pinfunction "S_16") (pintype "passive"))
    )
    (net (code "74") (name "Net-(X5J-S)") (class "Default")
      (node (ref "R35") (pin "1") (pinfunction "1_1") (pintype "passive"))
      (node (ref "X5") (pin "18") (pinfunction "S_18") (pintype "passive"))
    )
    (net (code "75") (name "Net-(X5K-S)") (class "Default")
      (node (ref "R43") (pin "1") (pinfunction "1_1") (pintype "passive"))
      (node (ref "X5") (pin "19") (pinfunction "S_19") (pintype "passive"))
    )
    (net (code "76") (name "Net-(X5L-S)") (class "Default")
      (node (ref "R20") (pin "1") (pinfunction "1_1") (pintype "passive"))
      (node (ref "X5") (pin "2") (pinfunction "S_2") (pintype "passive"))
    )
    (net (code "77") (name "Net-(X5M-S)") (class "Default")
      (node (ref "R36") (pin "1") (pinfunction "1_1") (pintype "passive"))
      (node (ref "X5") (pin "20") (pinfunction "S_20") (pintype "passive"))
    )
    (net (code "78") (name "Net-(X5O-S)") (class "Default")
      (node (ref "R37") (pin "1") (pinfunction "1_1") (pintype "passive"))
      (node (ref "X5") (pin "22") (pinfunction "S_22") (pintype "passive"))
    )
    (net (code "79") (name "Net-(X5P-S)") (class "Default")
      (node (ref "R44") (pin "1") (pinfunction "1_1") (pintype "passive"))
      (node (ref "X5") (pin "23") (pinfunction "S_23") (pintype "passive"))
    )
    (net (code "80") (name "Net-(X5Q-S)") (class "Default")
      (node (ref "R38") (pin "1") (pinfunction "1_1") (pintype "passive"))
      (node (ref "X5") (pin "24") (pinfunction "S_24") (pintype "passive"))
    )
    (net (code "81") (name "Net-(X5S-S)") (class "Default")
      (node (ref "R39") (pin "1") (pinfunction "1_1") (pintype "passive"))
      (node (ref "X5") (pin "26") (pinfunction "S_26") (pintype "passive"))
    )
    (net (code "82") (name "Net-(X5U-S)") (class "Default")
      (node (ref "R22") (pin "1") (pinfunction "1_1") (pintype "passive"))
      (node (ref "X5") (pin "4") (pinfunction "S_4") (pintype "passive"))
    )
    (net (code "83") (name "Net-(X5W-S)") (class "Default")
      (node (ref "R24") (pin "1") (pinfunction "1_1") (pintype "passive"))
      (node (ref "X5") (pin "6") (pinfunction "S_6") (pintype "passive"))
    )
    (net (code "84") (name "Net-(X5Y-S)") (class "Default")
      (node (ref "R26") (pin "1") (pinfunction "1_1") (pintype "passive"))
      (node (ref "X5") (pin "8") (pinfunction "S_8") (pintype "passive"))
    )
    (net (code "85") (name "REF") (class "Default")
      (node (ref "D8") (pin "C") (pinfunction "C_C") (pintype "passive"))
      (node (ref "IC1") (pin "11") (pinfunction "+IN_11") (pintype "input"))
      (node (ref "IC1") (pin "5") (pinfunction "+IN_5") (pintype "input"))
      (node (ref "IC1") (pin "7") (pinfunction "+IN_7") (pintype "input"))
      (node (ref "IC1") (pin "9") (pinfunction "+IN_9") (pintype "input"))
      (node (ref "IC2") (pin "11") (pinfunction "+IN_11") (pintype "input"))
      (node (ref "IC2") (pin "5") (pinfunction "+IN_5") (pintype "input"))
      (node (ref "IC2") (pin "7") (pinfunction "+IN_7") (pintype "input"))
      (node (ref "IC2") (pin "9") (pinfunction "+IN_9") (pintype "input"))
      (node (ref "R2") (pin "2") (pinfunction "2_2") (pintype "passive"))
    )
    (net (code "86") (name "SPARE") (class "Default")
      (node (ref "IC1") (pin "6") (pinfunction "-IN_6") (pintype "input"))
      (node (ref "R36") (pin "2") (pinfunction "2_2") (pintype "passive"))
      (node (ref "R41") (pin "2") (pinfunction "2_2") (pintype "passive"))
    )
    (net (code "87") (name "unconnected-(DCDC1-CTRL-Pad3)") (class "Default")
      (node (ref "DCDC1") (pin "3") (pinfunction "CTRL_3") (pintype "passive"))
    )
    (net (code "88") (name "unconnected-(DCDC1-NC-Pad4)") (class "Default")
      (node (ref "DCDC1") (pin "4") (pinfunction "NC_4") (pintype "passive"))
    )
    (net (code "89") (name "unconnected-(K1B-OA-Pad12A)") (class "Default")
      (node (ref "K1") (pin "12A") (pinfunction "OA_12A") (pintype "passive"))
    )
    (net (code "90") (name "unconnected-(K1B-OB-Pad12B)") (class "Default")
      (node (ref "K1") (pin "12B") (pinfunction "OB_12B") (pintype "passive"))
    )
    (net (code "91") (name "unconnected-(K2B-OA-Pad12A)") (class "Default")
      (node (ref "K2") (pin "12A") (pinfunction "OA_12A") (pintype "passive"))
    )
    (net (code "92") (name "unconnected-(K2B-OB-Pad12B)") (class "Default")
      (node (ref "K2") (pin "12B") (pinfunction "OB_12B") (pintype "passive"))
    )
    (net (code "93") (name "unconnected-(K3B-O-Pad12)") (class "Default")
      (node (ref "K3") (pin "12") (pinfunction "O_12") (pintype "passive"))
    )
    (net (code "94") (name "unconnected-(K3C-O-Pad22)") (class "Default")
      (node (ref "K3") (pin "22") (pinfunction "O_22") (pintype "passive"))
    )
    (net (code "95") (name "unconnected-(K4B-O-PadO1)") (class "Default")
      (node (ref "K4") (pin "O1") (pinfunction "O_O1") (pintype "passive"))
    )
    (net (code "96") (name "unconnected-(K4C-O-PadO2)") (class "Default")
      (node (ref "K4") (pin "O2") (pinfunction "O_O2") (pintype "passive"))
    )
    (net (code "97") (name "unconnected-(K5B-O-PadO1)") (class "Default")
      (node (ref "K5") (pin "O1") (pinfunction "O_O1") (pintype "passive"))
    )
    (net (code "98") (name "unconnected-(K5C-O-PadO2)") (class "Default")
      (node (ref "K5") (pin "O2") (pinfunction "O_O2") (pintype "passive"))
    )
    (net (code "99") (name "unconnected-(X1C-1-Pad3)") (class "Default")
      (node (ref "X1") (pin "3") (pinfunction "1_3") (pintype "passive"))
    )
  )
)
